# led_transistor.net
KiCad netlist of a schematic drawn in EAGLE
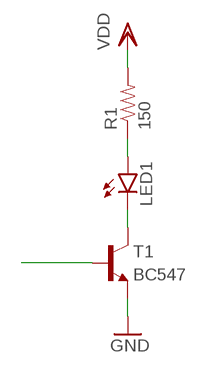
[diagram p0: schematic, sheet 1]

(export (version "E")
  (design (tool "Eeschema 10.0.6"))
  (components
    (comp (ref "LED1")
      (value "LED5MM")
      (footprint "eagle-import:LED5MM")
      (libsource (lib "eagle-import") (part "LED5MM"))
    )
    (comp (ref "R1")
      (value "150")
      (footprint "eagle-import:AXIAL-0.5")
      (libsource (lib "eagle-import") (part "RESISTORPTH-1/2W"))
    )
    (comp (ref "T1")
      (value "BC547")
      (footprint "eagle-import:TO92")
      (libsource (lib "eagle-import") (part "BC547"))
    )
  )
  (nets
    (net (code "1") (name "GND") (class "Default")
      (node (ref "T1") (pin "1") (pinfunction "E_1") (pintype "passive"))
    )
    (net (code "2") (name "Net-(LED1-C)") (class "Default")
      (node (ref "LED1") (pin "K") (pinfunction "C_K") (pintype "passive"))
      (node (ref "T1") (pin "3") (pinfunction "C_3") (pintype "passive"))
    )
    (net (code "3") (name "Net-(R1-1)") (class "Default")
      (node (ref "LED1") (pin "A") (pinfunction "A_A") (pintype "passive"))
      (node (ref "R1") (pin "P$1") (pinfunction "1_P$1") (pintype "passive"))
    )
    (net (code "4") (name "VDD") (class "Default")
      (node (ref "R1") (pin "P$2") (pinfunction "2_P$2") (pintype "passive"))
    )
    (net (code "5") (name "unconnected-(T1-B-Pad2)") (class "Default")
      (node (ref "T1") (pin "2") (pinfunction "B_2") (pintype "passive"))
    )
  )
)
